# PADS_Schemat.net
KiCad netlist of a schematic drawn in Altium Designer
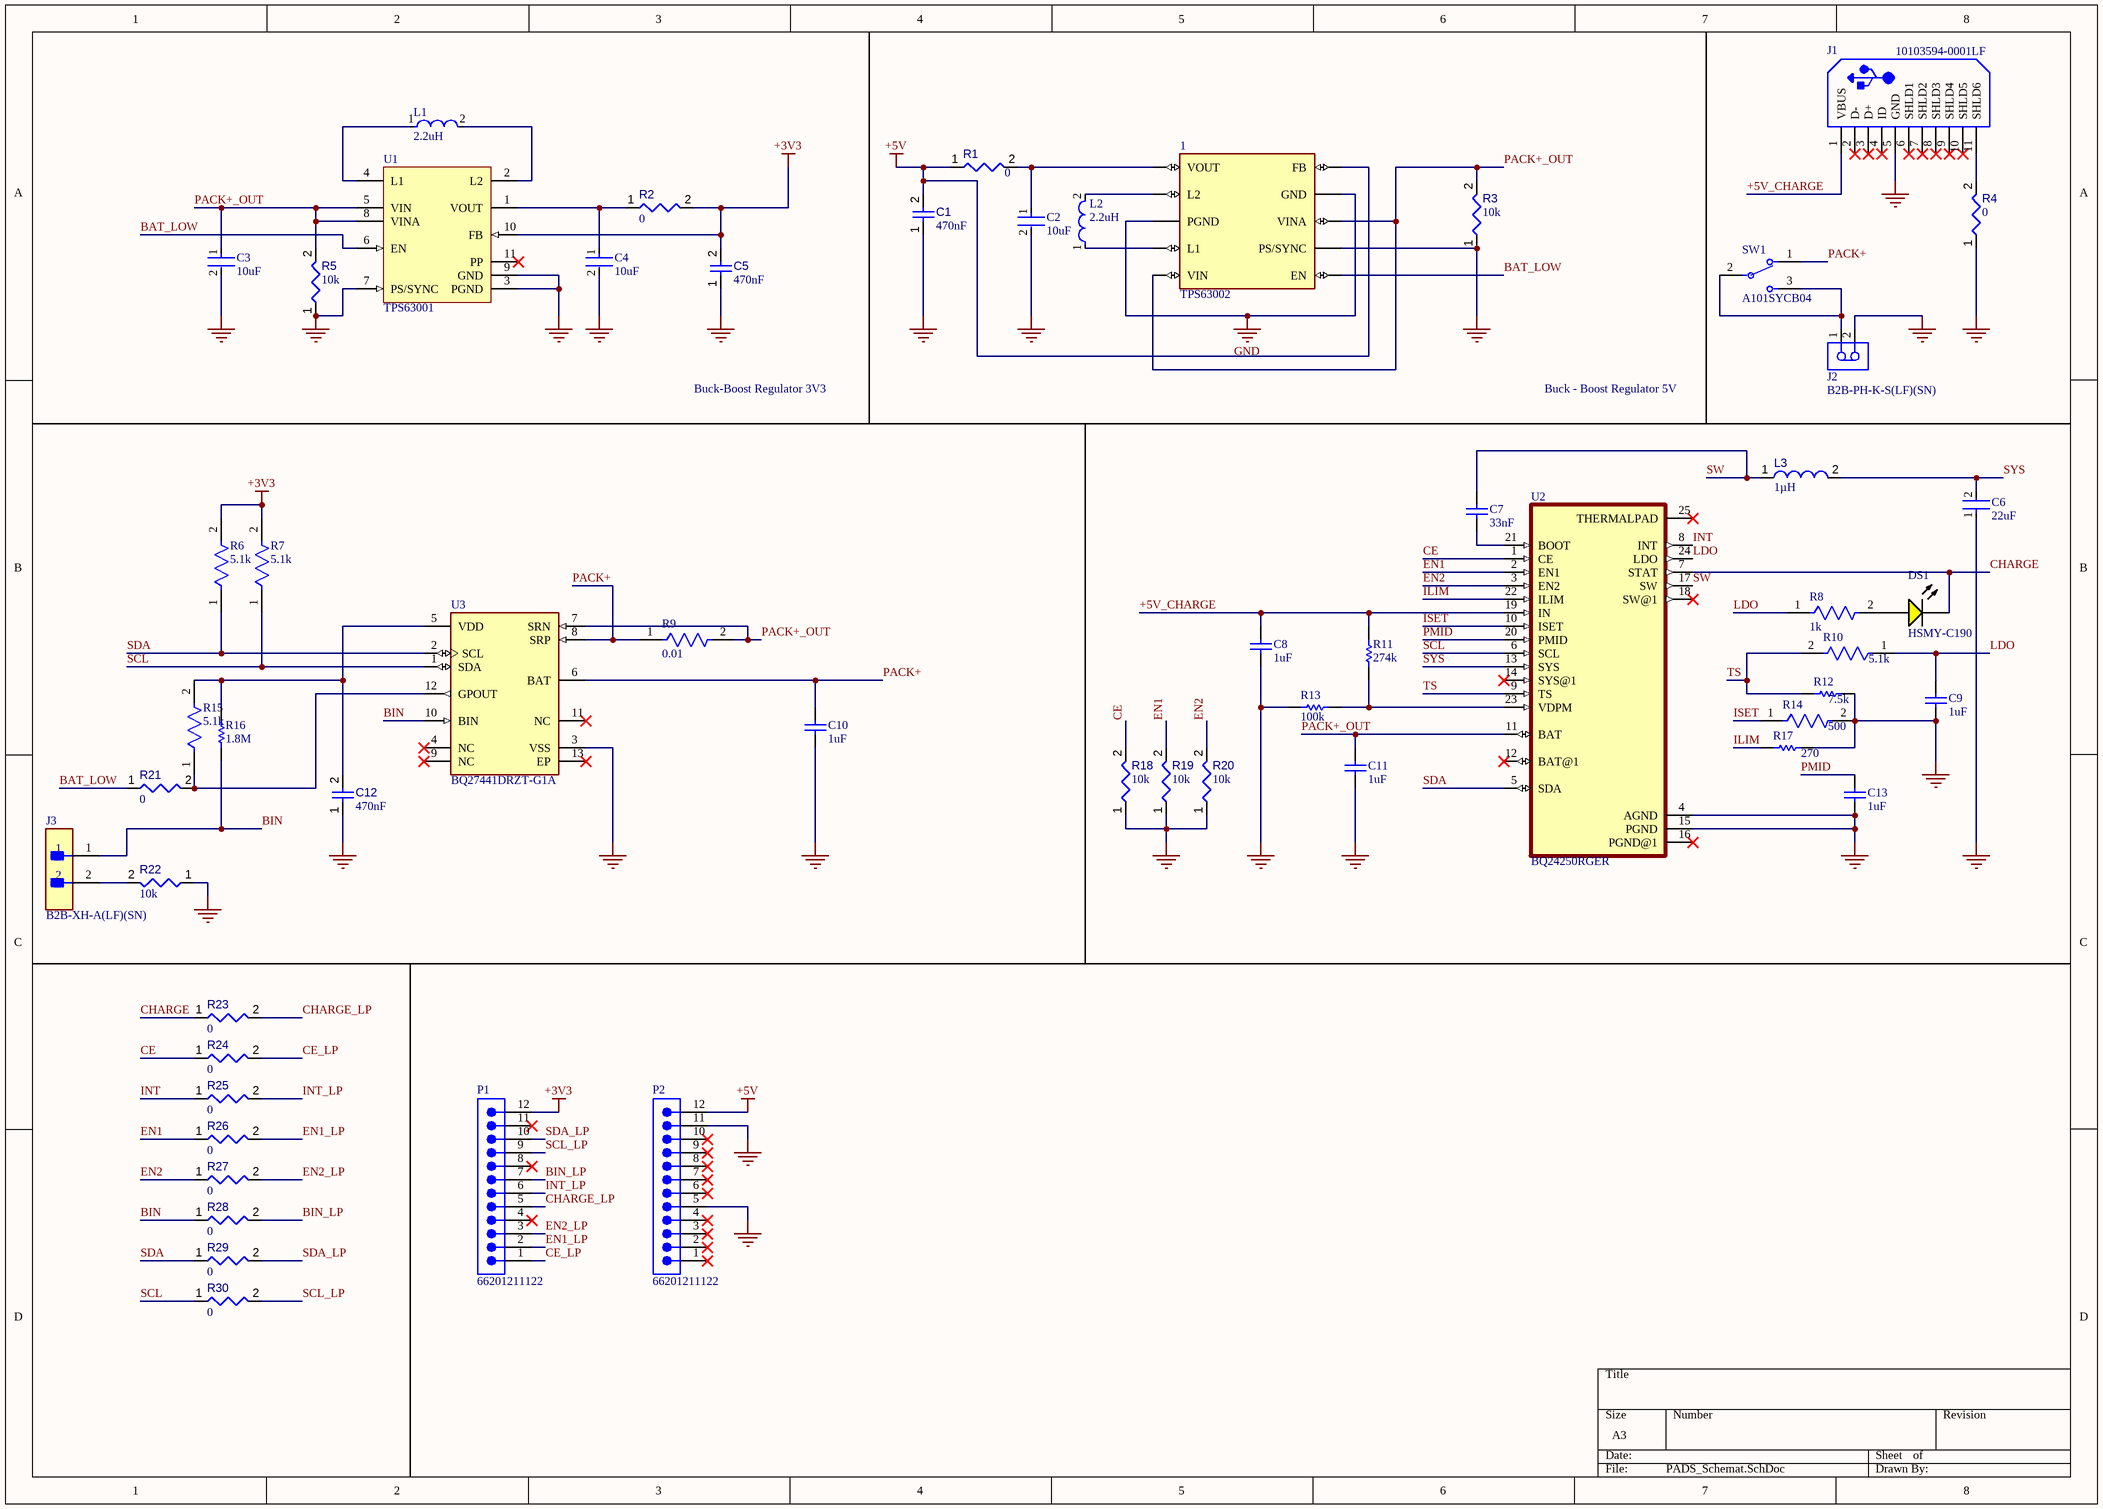
[diagram p0: PADS_Schemat.SchDoc]

(export (version "E")
  (design (tool "Eeschema 10.0.6"))
  (components
    (comp (ref "1")
      (value "TPS63002")
      (footprint "10SON")
      (description "Buck-Boost Switching Regulator IC Positive Fixed 5V 1 Output 1.6A _Switch_ 10-VFDFN Exposed Pad")
      (fields (field (name "MF") "Texas Instruments"))
      (libsource (lib "Przemysław Ziencik") (part "TPS63002"))
    )
    (comp (ref "C1")
      (value "470nF")
      (footprint "CAPC0603(1608)100_L")
      (description "Chip Capacitor, 470nF +/-20%, 25V, 0603, Thickness 1 mm")
      (fields (field (name "TOLERANCE") "10%") (field (name "Comment") "Capacitor 470nF +/-20% 25V 0603"))
      (libsource (lib "Przemysław Ziencik") (part "CAP-NP-2"))
    )
    (comp (ref "C2")
      (value "10uF")
      (footprint "FP-GRM188-0_1-e0_2_0_55-IPC_A")
      (description "Chip Multilayer Ceramic Capacitors for General Purpose, 0603, 10uF, X5R, 15%, 20%, 6.3V")
      (fields (field (name "VOLTAGE") "6.3V") (field (name "TOLERANCE") "20%"))
      (libsource (lib "Altium Content Vault") (part "02cd4be3c70576c341d710602a673aa"))
    )
    (comp (ref "C3")
      (value "10uF")
      (footprint "FP-GRM188-0_1-e0_2_0_55-IPC_A")
      (description "Chip Multilayer Ceramic Capacitors for General Purpose, 0603, 10uF, X5R, 15%, 20%, 6.3V")
      (fields (field (name "VOLTAGE") "6.3V") (field (name "TOLERANCE") "20%"))
      (libsource (lib "Altium Content Vault") (part "02cd4be3c70576c341d710602a673aa"))
    )
    (comp (ref "C4")
      (value "10uF")
      (footprint "FP-GRM188-0_1-e0_2_0_55-IPC_A")
      (description "Chip Multilayer Ceramic Capacitors for General Purpose, 0603, 10uF, X5R, 15%, 20%, 6.3V")
      (fields (field (name "VOLTAGE") "6.3V") (field (name "TOLERANCE") "20%"))
      (libsource (lib "Altium Content Vault") (part "02cd4be3c70576c341d710602a673aa"))
    )
    (comp (ref "C5")
      (value "470nF")
      (footprint "CAPC0603(1608)100_L")
      (description "Chip Capacitor, 470nF +/-20%, 25V, 0603, Thickness 1 mm")
      (fields (field (name "TOLERANCE") "10%") (field (name "Comment") "Capacitor 470nF +/-20% 25V 0603"))
      (libsource (lib "Przemysław Ziencik") (part "CAP-NP-2"))
    )
    (comp (ref "C6")
      (value "22uF")
      (footprint "FP-GRM21B-0_15-MFG")
      (description "Chip Multilayer Ceramic Capacitors for General Purpose, 0805, 22uF, X5R, 15%, 20%, 6.3V")
      (fields (field (name "VOLTAGE") "6.3V") (field (name "TOLERANCE") "20%"))
      (libsource (lib "Altium Content Vault") (part "b4654b650e69147ec39a6b967a45e02"))
    )
    (comp (ref "C7")
      (value "33nF")
      (footprint "CAPC2013X95X45NL10T25")
      (fields (field (name "MANUFACTURER") "Murata") (field (name "PART NUMBER") "GRM219R71H333KA01D"))
      (libsource (lib "Altium Content Vault") (part "CAP"))
    )
    (comp (ref "C8")
      (value "1uF")
      (footprint "CAPC2013X135X45LL10T25")
      (fields (field (name "MANUFACTURER") "Murata") (field (name "PART NUMBER") "GRM21BR71C105KA01K"))
      (libsource (lib "Altium Content Vault") (part "CAP"))
    )
    (comp (ref "C9")
      (value "1uF")
      (footprint "CAPC2013X135X45LL10T25")
      (fields (field (name "MANUFACTURER") "Murata") (field (name "PART NUMBER") "GRM21BR71C105KA01K"))
      (libsource (lib "Altium Content Vault") (part "CAP"))
    )
    (comp (ref "C10")
      (value "1uF")
      (footprint "CAPC2013X135X45LL10T25")
      (fields (field (name "MANUFACTURER") "Murata") (field (name "PART NUMBER") "GRM21BR71C105KA01K"))
      (libsource (lib "Altium Content Vault") (part "CAP"))
    )
    (comp (ref "C11")
      (value "1uF")
      (footprint "CAPC2013X135X45LL10T25")
      (fields (field (name "MANUFACTURER") "Murata") (field (name "PART NUMBER") "GRM21BR71C105KA01K"))
      (libsource (lib "Altium Content Vault") (part "CAP"))
    )
    (comp (ref "C12")
      (value "470nF")
      (footprint "CAPC0603(1608)100_L")
      (description "Chip Capacitor, 470nF +/-20%, 25V, 0603, Thickness 1 mm")
      (fields (field (name "TOLERANCE") "10%") (field (name "Comment") "Capacitor 470nF +/-20% 25V 0603"))
      (libsource (lib "Przemysław Ziencik") (part "CAP-NP-2"))
    )
    (comp (ref "C13")
      (value "1uF")
      (footprint "CAPC2013X135X45LL10T25")
      (fields (field (name "MANUFACTURER") "Murata") (field (name "PART NUMBER") "GRM21BR71C105KA01K"))
      (libsource (lib "Altium Content Vault") (part "CAP"))
    )
    (comp (ref "DS1")
      (value "HSMY-C190")
      (footprint "AVAG-HSMX-C190_V")
      (description "LED Uni-Color Yellow, 65 mW, 20 mA, -40 to 85 degC, 2-Pin SMD, RoHS, Tape and Reel")
      (fields (field (name "TOLERANCE") "1%"))
      (libsource (lib "Altium Content Vault") (part "LED-YELLOW-AK-2"))
    )
    (comp (ref "J1")
      (value "10103594-0001LF")
      (footprint "FCI-10103594-0001LF_V")
      (description "Micro USB 2.0 B Receptacle, 5 Position, Height 3.24 mm, -55 to 85 degC, RoHS, Tape and Reel")
      (fields (field (name "MANUFACTURER") "FCI Electronics"))
      (libsource (lib "Przemysław Ziencik") (part "USB-5-6SHLD"))
    )
    (comp (ref "J2")
      (value "B2B-PH-K-S(LF)(SN)")
      (footprint "JST-B2B-PH-K-S_V")
      (fields (field (name "MANUFACTURER") "JST"))
      (libsource (lib "Altium Content Vault") (part "CN-2P-F-QF2"))
    )
    (comp (ref "J3")
      (value "B2B-XH-A(LF)(SN)")
      (footprint "FP-B2B-XH-A_LF_SN-MFG")
      (description "CONN HEADER VERT 2POS 2.5MM")
      (libsource (lib "Altium Content Vault") (part "3bc925449376181038e59eaffc5286c"))
    )
    (comp (ref "L1")
      (value "2.2uH")
      (footprint "FP-LQM21PH_G0-IPC_C")
      (description "Multilayer Type Inductor for Power Lines, 0805 (2012), 2.2μH, 30%, 0.288Ω, 0.8A")
      (fields (field (name "TOLERANCE") "30%"))
      (libsource (lib "Altium Content Vault") (part "725321dda6339637d4d059423bc1c3c"))
    )
    (comp (ref "L2")
      (value "2.2uH")
      (footprint "FP-LQM21PH_G0-IPC_C")
      (description "Multilayer Type Inductor for Power Lines, 0805 (2012), 2.2μH, 30%, 0.288Ω, 0.8A")
      (fields (field (name "TOLERANCE") "30%"))
      (libsource (lib "Altium Content Vault") (part "725321dda6339637d4d059423bc1c3c"))
    )
    (comp (ref "L3")
      (value "1µH")
      (footprint "INDC2520X120X60NL20T20")
      (description "Chip Inductor, 1 uH, +/- 20%, 1 MHz, -55 to 125 degC, 1008 (2520 Metric), RoHS, Tape and Reel")
      (fields (field (name "TOLERANCE") "20%") (field (name "MANUFACTURER") "Murata"))
      (libsource (lib "Przemysław Ziencik") (part "IND-2"))
    )
    (comp (ref "P1")
      (value "66201211122")
      (footprint "66201211122")
      (libsource (lib "Altium Content Vault") (part "Header_Male_1R_12P"))
    )
    (comp (ref "P2")
      (value "66201211122")
      (footprint "66201211122")
      (libsource (lib "Altium Content Vault") (part "Header_Male_1R_12P"))
    )
    (comp (ref "R1")
      (value "0")
      (footprint "RESC0603(1608)_L")
      (description "Jumper 0603 (1608 Metric)")
      (fields (field (name "Comment") "0R3J"))
      (libsource (lib "Przemysław Ziencik") (part "0R3J"))
    )
    (comp (ref "R2")
      (value "0")
      (footprint "RESC0603(1608)_L")
      (description "Jumper 0603 (1608 Metric)")
      (fields (field (name "Comment") "0R3J"))
      (libsource (lib "Przemysław Ziencik") (part "0R3J"))
    )
    (comp (ref "R3")
      (value "10k")
      (footprint "RESC0402(1005)_L")
      (description "10K 0.063W 1% 0402 (1005 Metric)  SMD")
      (fields (field (name "POWER") "63mW") (field (name "TOLERANCE") "1%"))
      (libsource (lib "Przemysław Ziencik") (part "10KR2F"))
    )
    (comp (ref "R4")
      (value "0")
      (footprint "RESC0603(1608)_L")
      (description "Jumper 0603 (1608 Metric)")
      (fields (field (name "Comment") "0R3J"))
      (libsource (lib "Przemysław Ziencik") (part "0R3J"))
    )
    (comp (ref "R5")
      (value "10k")
      (footprint "RESC0402(1005)_L")
      (description "10K 0.063W 1% 0402 (1005 Metric)  SMD")
      (fields (field (name "POWER") "63mW") (field (name "TOLERANCE") "1%"))
      (libsource (lib "Przemysław Ziencik") (part "10KR2F"))
    )
    (comp (ref "R6")
      (value "5.1k")
      (footprint "FP-CRCW0603-e3-IPC_C")
      (description "RES Thick Film, 5.1kΩ, 1%, 0.1W, 100ppm/°C, 0603")
      (fields (field (name "TOLERANCE") "1%"))
      (libsource (lib "Altium Content Vault") (part "1029c3af85768c4190bb7ad29bc67b5"))
    )
    (comp (ref "R7")
      (value "5.1k")
      (footprint "FP-CRCW0603-e3-IPC_C")
      (description "RES Thick Film, 5.1kΩ, 1%, 0.1W, 100ppm/°C, 0603")
      (fields (field (name "TOLERANCE") "1%"))
      (libsource (lib "Altium Content Vault") (part "1029c3af85768c4190bb7ad29bc67b5"))
    )
    (comp (ref "R8")
      (value "1k")
      (footprint "FP-ERA3A-IPC_C")
      (description "RES SMD 1K OHM 0.1% 1/10W 0603")
      (fields (field (name "TOLERANCE") "0.1%"))
      (libsource (lib "Altium Content Vault") (part "1029c3af85768c4190bb7ad29bc67b5"))
    )
    (comp (ref "R9")
      (value "0.01")
      (footprint "FP-ERJ8CW-MFG")
      (description "RES 0.01 OHM 1% 1W 1206")
      (fields (field (name "TOLERANCE") "1%"))
      (libsource (lib "Altium Content Vault") (part "1029c3af85768c4190bb7ad29bc67b5"))
    )
    (comp (ref "R10")
      (value "5.1k")
      (footprint "FP-CRCW0603-e3-IPC_C")
      (description "RES Thick Film, 5.1kΩ, 1%, 0.1W, 100ppm/°C, 0603")
      (fields (field (name "TOLERANCE") "1%"))
      (libsource (lib "Altium Content Vault") (part "1029c3af85768c4190bb7ad29bc67b5"))
    )
    (comp (ref "R11")
      (value "274k")
      (footprint "RESC1608X55X30NL15T15")
      (fields (field (name "MANUFACTURER") "Panasonic") (field (name "PART NUMBER") "ERJ-3EKF2743V"))
      (libsource (lib "Altium Content Vault") (part "RES"))
    )
    (comp (ref "R12")
      (value "7.5k")
      (footprint "RESC1609X55X30NL10T20")
      (fields (field (name "PART NUMBER") "TNPW06037K50BEEA") (field (name "MANUFACTURER") "Vishay Dale"))
      (libsource (lib "Altium Content Vault") (part "RES"))
    )
    (comp (ref "R13")
      (value "100k")
      (footprint "RESC2013X70X40NL20T20")
      (fields (field (name "PART NUMBER") "ERJ-6GEYJ104V") (field (name "MANUFACTURER") "Panasonic"))
      (libsource (lib "Altium Content Vault") (part "RES"))
    )
    (comp (ref "R14")
      (value "500")
      (footprint "FP-MCT0603-MFG")
      (description "RES SMD 100 OHM 1% 1/8W 0603")
      (fields (field (name "TOLERANCE") "0.1%"))
      (libsource (lib "Altium Content Vault") (part "1029c3af85768c4190bb7ad29bc67b5"))
    )
    (comp (ref "R15")
      (value "5.1k")
      (footprint "FP-CRCW0603-e3-IPC_C")
      (description "RES Thick Film, 5.1kΩ, 1%, 0.1W, 100ppm/°C, 0603")
      (fields (field (name "TOLERANCE") "1%"))
      (libsource (lib "Altium Content Vault") (part "1029c3af85768c4190bb7ad29bc67b5"))
    )
    (comp (ref "R16")
      (value "1.8M")
      (footprint "RESC1608X55X30ML15T15")
      (fields (field (name "MANUFACTURER") "Panasonic") (field (name "PART NUMBER") "ERJ-3EKF1804V"))
      (libsource (lib "Altium Content Vault") (part "RES"))
    )
    (comp (ref "R17")
      (value "270")
      (footprint "RESC1608X55X30LL15T15")
      (fields (field (name "MANUFACTURER") "Panasonic") (field (name "PART NUMBER") "ERJ3EKF2700V"))
      (libsource (lib "Altium Content Vault") (part "RES"))
    )
    (comp (ref "R18")
      (value "10k")
      (footprint "RESC0402(1005)_L")
      (description "10K 0.063W 1% 0402 (1005 Metric)  SMD")
      (fields (field (name "POWER") "63mW") (field (name "TOLERANCE") "1%"))
      (libsource (lib "Przemysław Ziencik") (part "10KR2F"))
    )
    (comp (ref "R19")
      (value "10k")
      (footprint "RESC0402(1005)_L")
      (description "10K 0.063W 1% 0402 (1005 Metric)  SMD")
      (fields (field (name "POWER") "63mW") (field (name "TOLERANCE") "1%"))
      (libsource (lib "Przemysław Ziencik") (part "10KR2F"))
    )
    (comp (ref "R20")
      (value "10k")
      (footprint "RESC0402(1005)_L")
      (description "10K 0.063W 1% 0402 (1005 Metric)  SMD")
      (fields (field (name "POWER") "63mW") (field (name "TOLERANCE") "1%"))
      (libsource (lib "Przemysław Ziencik") (part "10KR2F"))
    )
    (comp (ref "R21")
      (value "0")
      (footprint "RESC0603(1608)_L")
      (description "Jumper 0603 (1608 Metric)")
      (fields (field (name "Comment") "0R3J"))
      (libsource (lib "Przemysław Ziencik") (part "0R3J"))
    )
    (comp (ref "R22")
      (value "10k")
      (footprint "RESC0402(1005)_L")
      (description "10K 0.063W 1% 0402 (1005 Metric)  SMD")
      (fields (field (name "POWER") "63mW") (field (name "TOLERANCE") "1%"))
      (libsource (lib "Przemysław Ziencik") (part "10KR2F"))
    )
    (comp (ref "R23")
      (value "0")
      (footprint "RESC0603(1608)_L")
      (description "Jumper 0603 (1608 Metric)")
      (fields (field (name "Comment") "0R3J"))
      (libsource (lib "Przemysław Ziencik") (part "0R3J"))
    )
    (comp (ref "R24")
      (value "0")
      (footprint "RESC0603(1608)_L")
      (description "Jumper 0603 (1608 Metric)")
      (fields (field (name "Comment") "0R3J"))
      (libsource (lib "Przemysław Ziencik") (part "0R3J"))
    )
    (comp (ref "R25")
      (value "0")
      (footprint "RESC0603(1608)_L")
      (description "Jumper 0603 (1608 Metric)")
      (fields (field (name "Comment") "0R3J"))
      (libsource (lib "Przemysław Ziencik") (part "0R3J"))
    )
    (comp (ref "R26")
      (value "0")
      (footprint "RESC0603(1608)_L")
      (description "Jumper 0603 (1608 Metric)")
      (fields (field (name "Comment") "0R3J"))
      (libsource (lib "Przemysław Ziencik") (part "0R3J"))
    )
    (comp (ref "R27")
      (value "0")
      (footprint "RESC0603(1608)_L")
      (description "Jumper 0603 (1608 Metric)")
      (fields (field (name "Comment") "0R3J"))
      (libsource (lib "Przemysław Ziencik") (part "0R3J"))
    )
    (comp (ref "R28")
      (value "0")
      (footprint "RESC0603(1608)_L")
      (description "Jumper 0603 (1608 Metric)")
      (fields (field (name "Comment") "0R3J"))
      (libsource (lib "Przemysław Ziencik") (part "0R3J"))
    )
    (comp (ref "R29")
      (value "0")
      (footprint "RESC0603(1608)_L")
      (description "Jumper 0603 (1608 Metric)")
      (fields (field (name "Comment") "0R3J"))
      (libsource (lib "Przemysław Ziencik") (part "0R3J"))
    )
    (comp (ref "R30")
      (value "0")
      (footprint "RESC0603(1608)_L")
      (description "Jumper 0603 (1608 Metric)")
      (fields (field (name "Comment") "0R3J"))
      (libsource (lib "Przemysław Ziencik") (part "0R3J"))
    )
    (comp (ref "SW1")
      (value "A101SYCB04")
      (footprint "FP-A101SYCB04-MFG")
      (description "SWITCH TOGGLE SPDT 0.4VA 20V")
      (libsource (lib "Altium Content Vault") (part "52c419afdc2a387c7d548259a9aeefb"))
    )
    (comp (ref "U1")
      (value "TPS63001")
      (footprint "DRC0010J_V")
      (fields (field (name "PARTNUMBER") "TPS63001DRCR") (field (name "MANUFACTURER") "Texas Instruments"))
      (libsource (lib "Altium Content Vault") (part "TI-TPS63001DRC10-3000X1650TP"))
    )
    (comp (ref "U2")
      (value "BQ24250RGER")
      (footprint "QFN50P400X400X100-25N")
      (fields (field (name "MF") "Texas Instruments"))
      (libsource (lib "BQ24250RGER") (part "BQ24250RGER"))
    )
    (comp (ref "U3")
      (value "BQ27441DRZT-G1A")
      (footprint "FP-DRZ0012A-MFG")
      (description "IC BATT FUEL GAUGE LICOO2 12SON")
      (fields
        (field (name "OCTOPART") "https://octopart.com/bq27441drzt-g1a-texas+instruments-30555831")
        (field (name "MANUFACTURER") "Texas Instruments")
      )
      (libsource (lib "Altium Content Vault") (part "c803e035ce0891ae19034f27297cdee"))
    )
  )
  (nets
    (net (code "1") (name "+3V3") (class "Default")
      (node (ref "C5") (pin "2") (pinfunction "2_2") (pintype "passive"))
      (node (ref "P1") (pin "12") (pinfunction "12_12") (pintype "passive"))
      (node (ref "R2") (pin "2") (pinfunction "2_2") (pintype "passive"))
      (node (ref "R6") (pin "2") (pinfunction "2_2") (pintype "passive"))
      (node (ref "R7") (pin "2") (pinfunction "2_2") (pintype "passive"))
      (node (ref "U1") (pin "10") (pinfunction "FB_10") (pintype "input"))
    )
    (net (code "2") (name "+5V") (class "Default")
      (node (ref "1") (pin "P$10") (pinfunction "FB_P$10") (pintype "bidirectional"))
      (node (ref "C1") (pin "2") (pinfunction "2_2") (pintype "passive"))
      (node (ref "P2") (pin "12") (pinfunction "12_12") (pintype "passive"))
      (node (ref "R1") (pin "1") (pinfunction "1_1") (pintype "passive"))
    )
    (net (code "3") (name "/+5V_CHARGE") (class "Default")
      (node (ref "C8") (pin "2") (pinfunction "2_2") (pintype "passive"))
      (node (ref "J1") (pin "1") (pinfunction "VBUS_1") (pintype "passive"))
      (node (ref "R11") (pin "2") (pinfunction "2_2") (pintype "passive"))
      (node (ref "U2") (pin "19") (pinfunction "IN_19") (pintype "input"))
    )
    (net (code "4") (name "/BAT_LOW") (class "Default")
      (node (ref "1") (pin "P$6") (pinfunction "EN_P$6") (pintype "bidirectional"))
      (node (ref "R21") (pin "1") (pinfunction "1_1") (pintype "passive"))
      (node (ref "U1") (pin "6") (pinfunction "EN_6") (pintype "input"))
    )
    (net (code "5") (name "/BIN") (class "Default")
      (node (ref "J3") (pin "1") (pinfunction "1_1") (pintype "passive"))
      (node (ref "R16") (pin "1") (pinfunction "1_1") (pintype "passive"))
      (node (ref "R28") (pin "1") (pinfunction "1_1") (pintype "passive"))
      (node (ref "U3") (pin "10") (pinfunction "BIN_10") (pintype "input"))
    )
    (net (code "6") (name "/BIN_LP") (class "Default")
      (node (ref "P1") (pin "7") (pinfunction "7_7") (pintype "passive"))
      (node (ref "R28") (pin "2") (pinfunction "2_2") (pintype "passive"))
    )
    (net (code "7") (name "/CE") (class "Default")
      (node (ref "R18") (pin "2") (pinfunction "2_2") (pintype "passive"))
      (node (ref "R24") (pin "1") (pinfunction "1_1") (pintype "passive"))
      (node (ref "U2") (pin "1") (pinfunction "CE_1") (pintype "input"))
    )
    (net (code "8") (name "/CE_LP") (class "Default")
      (node (ref "P1") (pin "1") (pinfunction "1_1") (pintype "passive"))
      (node (ref "R24") (pin "2") (pinfunction "2_2") (pintype "passive"))
    )
    (net (code "9") (name "/CHARGE") (class "Default")
      (node (ref "DS1") (pin "2") (pinfunction "K_2") (pintype "passive"))
      (node (ref "R23") (pin "1") (pinfunction "1_1") (pintype "passive"))
      (node (ref "U2") (pin "7") (pinfunction "STAT_7") (pintype "output"))
    )
    (net (code "10") (name "/CHARGE_LP") (class "Default")
      (node (ref "P1") (pin "5") (pinfunction "5_5") (pintype "passive"))
      (node (ref "R23") (pin "2") (pinfunction "2_2") (pintype "passive"))
    )
    (net (code "11") (name "/EN1") (class "Default")
      (node (ref "R19") (pin "2") (pinfunction "2_2") (pintype "passive"))
      (node (ref "R26") (pin "1") (pinfunction "1_1") (pintype "passive"))
      (node (ref "U2") (pin "2") (pinfunction "EN1_2") (pintype "input"))
    )
    (net (code "12") (name "/EN1_LP") (class "Default")
      (node (ref "P1") (pin "2") (pinfunction "2_2") (pintype "passive"))
      (node (ref "R26") (pin "2") (pinfunction "2_2") (pintype "passive"))
    )
    (net (code "13") (name "/EN2") (class "Default")
      (node (ref "R20") (pin "2") (pinfunction "2_2") (pintype "passive"))
      (node (ref "R27") (pin "1") (pinfunction "1_1") (pintype "passive"))
      (node (ref "U2") (pin "3") (pinfunction "EN2_3") (pintype "input"))
    )
    (net (code "14") (name "/EN2_LP") (class "Default")
      (node (ref "P1") (pin "3") (pinfunction "3_3") (pintype "passive"))
      (node (ref "R27") (pin "2") (pinfunction "2_2") (pintype "passive"))
    )
    (net (code "15") (name "/ILIM") (class "Default")
      (node (ref "R17") (pin "1") (pinfunction "1_1") (pintype "passive"))
      (node (ref "U2") (pin "22") (pinfunction "ILIM_22") (pintype "input"))
    )
    (net (code "16") (name "/INT") (class "Default")
      (node (ref "R25") (pin "1") (pinfunction "1_1") (pintype "passive"))
      (node (ref "U2") (pin "8") (pinfunction "INT_8") (pintype "output"))
    )
    (net (code "17") (name "/INT_LP") (class "Default")
      (node (ref "P1") (pin "6") (pinfunction "6_6") (pintype "passive"))
      (node (ref "R25") (pin "2") (pinfunction "2_2") (pintype "passive"))
    )
    (net (code "18") (name "/ISET") (class "Default")
      (node (ref "R14") (pin "1") (pinfunction "1_1") (pintype "passive"))
      (node (ref "U2") (pin "10") (pinfunction "ISET_10") (pintype "input"))
    )
    (net (code "19") (name "/LDO") (class "Default")
      (node (ref "C9") (pin "2") (pinfunction "2_2") (pintype "passive"))
      (node (ref "R10") (pin "1") (pinfunction "1_1") (pintype "passive"))
      (node (ref "R8") (pin "1") (pinfunction "1_1") (pintype "passive"))
      (node (ref "U2") (pin "24") (pinfunction "LDO_24") (pintype "output"))
    )
    (net (code "20") (name "/PACK+") (class "Default")
      (node (ref "C10") (pin "2") (pinfunction "2_2") (pintype "passive"))
      (node (ref "R9") (pin "1") (pinfunction "1_1") (pintype "passive"))
      (node (ref "SW1") (pin "1") (pinfunction "1_1") (pintype "passive"))
      (node (ref "U3") (pin "6") (pinfunction "BAT_6") (pintype "power_in"))
      (node (ref "U3") (pin "8") (pinfunction "SRP_8") (pintype "input"))
    )
    (net (code "21") (name "/PACK+_OUT") (class "Default")
      (node (ref "1") (pin "P$5") (pinfunction "VIN_P$5") (pintype "bidirectional"))
      (node (ref "1") (pin "P$8") (pinfunction "VINA_P$8") (pintype "bidirectional"))
      (node (ref "C11") (pin "2") (pinfunction "2_2") (pintype "passive"))
      (node (ref "C3") (pin "1") (pinfunction "1_1") (pintype "passive"))
      (node (ref "R3") (pin "2") (pinfunction "2_2") (pintype "passive"))
      (node (ref "R5") (pin "2") (pinfunction "2_2") (pintype "passive"))
      (node (ref "R9") (pin "2") (pinfunction "2_2") (pintype "passive"))
      (node (ref "U1") (pin "5") (pinfunction "VIN_5") (pintype "passive"))
      (node (ref "U1") (pin "8") (pinfunction "VINA_8") (pintype "passive"))
      (node (ref "U2") (pin "11") (pinfunction "BAT_11") (pintype "bidirectional"))
      (node (ref "U3") (pin "7") (pinfunction "SRN_7") (pintype "input"))
    )
    (net (code "22") (name "/PMID") (class "Default")
      (node (ref "C13") (pin "2") (pinfunction "2_2") (pintype "passive"))
      (node (ref "U2") (pin "20") (pinfunction "PMID_20") (pintype "input"))
    )
    (net (code "23") (name "/SCL") (class "Default")
      (node (ref "R30") (pin "1") (pinfunction "1_1") (pintype "passive"))
      (node (ref "R7") (pin "1") (pinfunction "1_1") (pintype "passive"))
      (node (ref "U2") (pin "6") (pinfunction "SCL_6") (pintype "input"))
      (node (ref "U3") (pin "1") (pinfunction "SDA_1") (pintype "bidirectional"))
    )
    (net (code "24") (name "/SCL_LP") (class "Default")
      (node (ref "P1") (pin "9") (pinfunction "9_9") (pintype "passive"))
      (node (ref "R30") (pin "2") (pinfunction "2_2") (pintype "passive"))
    )
    (net (code "25") (name "/SDA") (class "Default")
      (node (ref "R29") (pin "1") (pinfunction "1_1") (pintype "passive"))
      (node (ref "R6") (pin "1") (pinfunction "1_1") (pintype "passive"))
      (node (ref "U2") (pin "5") (pinfunction "SDA_5") (pintype "bidirectional"))
      (node (ref "U3") (pin "2") (pinfunction "SCL_2") (pintype "bidirectional"))
    )
    (net (code "26") (name "/SDA_LP") (class "Default")
      (node (ref "P1") (pin "10") (pinfunction "10_10") (pintype "passive"))
      (node (ref "R29") (pin "2") (pinfunction "2_2") (pintype "passive"))
    )
    (net (code "27") (name "/SW") (class "Default")
      (node (ref "C7") (pin "2") (pinfunction "2_2") (pintype "passive"))
      (node (ref "L3") (pin "1") (pinfunction "1_1") (pintype "passive"))
      (node (ref "U2") (pin "17") (pinfunction "SW_17") (pintype "output"))
    )
    (net (code "28") (name "/SYS") (class "Default")
      (node (ref "C6") (pin "2") (pinfunction "2_2") (pintype "passive"))
      (node (ref "L3") (pin "2") (pinfunction "2_2") (pintype "passive"))
      (node (ref "U2") (pin "13") (pinfunction "SYS_13") (pintype "input"))
    )
    (net (code "29") (name "/TS") (class "Default")
      (node (ref "R10") (pin "2") (pinfunction "2_2") (pintype "passive"))
      (node (ref "R12") (pin "1") (pinfunction "1_1") (pintype "passive"))
      (node (ref "U2") (pin "9") (pinfunction "TS_9") (pintype "input"))
    )
    (net (code "30") (name "GND") (class "Default")
      (node (ref "1") (pin "P$3") (pinfunction "PGND_P$3") (pintype "passive"))
      (node (ref "1") (pin "P$7") (pinfunction "PS/SYNC_P$7") (pintype "passive"))
      (node (ref "1") (pin "P$9") (pinfunction "GND_P$9") (pintype "passive"))
      (node (ref "C1") (pin "1") (pinfunction "1_1") (pintype "passive"))
      (node (ref "C10") (pin "1") (pinfunction "1_1") (pintype "passive"))
      (node (ref "C11") (pin "1") (pinfunction "1_1") (pintype "passive"))
      (node (ref "C12") (pin "1") (pinfunction "1_1") (pintype "passive"))
      (node (ref "C13") (pin "1") (pinfunction "1_1") (pintype "passive"))
      (node (ref "C2") (pin "2") (pinfunction "2_2") (pintype "passive"))
      (node (ref "C3") (pin "2") (pinfunction "2_2") (pintype "passive"))
      (node (ref "C4") (pin "2") (pinfunction "2_2") (pintype "passive"))
      (node (ref "C5") (pin "1") (pinfunction "1_1") (pintype "passive"))
      (node (ref "C6") (pin "1") (pinfunction "1_1") (pintype "passive"))
      (node (ref "C8") (pin "1") (pinfunction "1_1") (pintype "passive"))
      (node (ref "C9") (pin "1") (pinfunction "1_1") (pintype "passive"))
      (node (ref "J1") (pin "5") (pinfunction "GND_5") (pintype "passive"))
      (node (ref "J2") (pin "2") (pinfunction "2_2") (pintype "passive"))
      (node (ref "P2") (pin "11") (pinfunction "11_11") (pintype "passive"))
      (node (ref "P2") (pin "5") (pinfunction "5_5") (pintype "passive"))
      (node (ref "R12") (pin "2") (pinfunction "2_2") (pintype "passive"))
      (node (ref "R13") (pin "1") (pinfunction "1_1") (pintype "passive"))
      (node (ref "R14") (pin "2") (pinfunction "2_2") (pintype "passive"))
      (node (ref "R17") (pin "2") (pinfunction "2_2") (pintype "passive"))
      (node (ref "R18") (pin "1") (pinfunction "1_1") (pintype "passive"))
      (node (ref "R19") (pin "1") (pinfunction "1_1") (pintype "passive"))
      (node (ref "R20") (pin "1") (pinfunction "1_1") (pintype "passive"))
      (node (ref "R22") (pin "1") (pinfunction "1_1") (pintype "passive"))
      (node (ref "R3") (pin "1") (pinfunction "1_1") (pintype "passive"))
      (node (ref "R4") (pin "1") (pinfunction "1_1") (pintype "passive"))
      (node (ref "R5") (pin "1") (pinfunction "1_1") (pintype "passive"))
      (node (ref "U1") (pin "3") (pinfunction "PGND_3") (pintype "passive"))
      (node (ref "U1") (pin "7") (pinfunction "PS/SYNC_7") (pintype "input"))
      (node (ref "U1") (pin "9") (pinfunction "GND_9") (pintype "passive"))
      (node (ref "U2") (pin "15") (pinfunction "PGND_15") (pintype "power_in"))
      (node (ref "U2") (pin "4") (pinfunction "AGND_4") (pintype "power_in"))
      (node (ref "U3") (pin "3") (pinfunction "VSS_3") (pintype "power_in"))
    )
    (net (code "31") (name "Net-(1-L1)") (class "Default")
      (node (ref "1") (pin "P$4") (pinfunction "L1_P$4") (pintype "bidirectional"))
      (node (ref "L2") (pin "1") (pinfunction "1_1") (pintype "passive"))
    )
    (net (code "32") (name "Net-(1-L2)") (class "Default")
      (node (ref "1") (pin "P$2") (pinfunction "L2_P$2") (pintype "bidirectional"))
      (node (ref "L2") (pin "2") (pinfunction "2_2") (pintype "passive"))
    )
    (net (code "33") (name "Net-(1-VOUT)") (class "Default")
      (node (ref "1") (pin "P$1") (pinfunction "VOUT_P$1") (pintype "bidirectional"))
      (node (ref "C2") (pin "1") (pinfunction "1_1") (pintype "passive"))
      (node (ref "R1") (pin "2") (pinfunction "2_2") (pintype "passive"))
    )
    (net (code "34") (name "Net-(DS1-A)") (class "Default")
      (node (ref "DS1") (pin "1") (pinfunction "A_1") (pintype "passive"))
      (node (ref "R8") (pin "2") (pinfunction "2_2") (pintype "passive"))
    )
    (net (code "35") (name "Net-(J1-SHLD6)") (class "Default")
      (node (ref "J1") (pin "11") (pinfunction "SHLD6_11") (pintype "passive"))
      (node (ref "R4") (pin "2") (pinfunction "2_2") (pintype "passive"))
    )
    (net (code "36") (name "Net-(J2-Pad1)") (class "Default")
      (node (ref "J2") (pin "1") (pinfunction "1_1") (pintype "passive"))
      (node (ref "SW1") (pin "2") (pinfunction "2_2") (pintype "passive"))
      (node (ref "SW1") (pin "3") (pinfunction "3_3") (pintype "passive"))
    )
    (net (code "37") (name "Net-(J3-Pad2)") (class "Default")
      (node (ref "J3") (pin "2") (pinfunction "2_2") (pintype "passive"))
      (node (ref "R22") (pin "2") (pinfunction "2_2") (pintype "passive"))
    )
    (net (code "38") (name "Net-(U1-L1)") (class "Default")
      (node (ref "L1") (pin "1") (pinfunction "1_1") (pintype "passive"))
      (node (ref "U1") (pin "4") (pinfunction "L1_4") (pintype "passive"))
    )
    (net (code "39") (name "Net-(U1-L2)") (class "Default")
      (node (ref "L1") (pin "2") (pinfunction "2_2") (pintype "passive"))
      (node (ref "U1") (pin "2") (pinfunction "L2_2") (pintype "passive"))
    )
    (net (code "40") (name "Net-(U1-VOUT)") (class "Default")
      (node (ref "C4") (pin "1") (pinfunction "1_1") (pintype "passive"))
      (node (ref "R2") (pin "1") (pinfunction "1_1") (pintype "passive"))
      (node (ref "U1") (pin "1") (pinfunction "VOUT_1") (pintype "power_in"))
    )
    (net (code "41") (name "Net-(U2-BOOT)") (class "Default")
      (node (ref "C7") (pin "1") (pinfunction "1_1") (pintype "passive"))
      (node (ref "U2") (pin "21") (pinfunction "BOOT_21") (pintype "input"))
    )
    (net (code "42") (name "Net-(U2-VDPM)") (class "Default")
      (node (ref "R11") (pin "1") (pinfunction "1_1") (pintype "passive"))
      (node (ref "R13") (pin "2") (pinfunction "2_2") (pintype "passive"))
      (node (ref "U2") (pin "23") (pinfunction "VDPM_23") (pintype "input"))
    )
    (net (code "43") (name "Net-(U3-GPOUT)") (class "Default")
      (node (ref "R15") (pin "1") (pinfunction "1_1") (pintype "passive"))
      (node (ref "R21") (pin "2") (pinfunction "2_2") (pintype "passive"))
      (node (ref "U3") (pin "12") (pinfunction "GPOUT_12") (pintype "output"))
    )
    (net (code "44") (name "Net-(U3-VDD)") (class "Default")
      (node (ref "C12") (pin "2") (pinfunction "2_2") (pintype "passive"))
      (node (ref "R15") (pin "2") (pinfunction "2_2") (pintype "passive"))
      (node (ref "R16") (pin "2") (pinfunction "2_2") (pintype "passive"))
      (node (ref "U3") (pin "5") (pinfunction "VDD_5") (pintype "power_in"))
    )
    (net (code "45") (name "unconnected-(J1-D+-Pad3)") (class "Default")
      (node (ref "J1") (pin "3") (pinfunction "D+_3") (pintype "passive+no_connect"))
    )
    (net (code "46") (name "unconnected-(J1-D--Pad2)") (class "Default")
      (node (ref "J1") (pin "2") (pinfunction "D-_2") (pintype "passive+no_connect"))
    )
    (net (code "47") (name "unconnected-(J1-ID-Pad4)") (class "Default")
      (node (ref "J1") (pin "4") (pinfunction "ID_4") (pintype "passive+no_connect"))
    )
    (net (code "48") (name "unconnected-(J1-SHLD1-Pad6)") (class "Default")
      (node (ref "J1") (pin "6") (pinfunction "SHLD1_6") (pintype "passive+no_connect"))
    )
    (net (code "49") (name "unconnected-(J1-SHLD2-Pad7)") (class "Default")
      (node (ref "J1") (pin "7") (pinfunction "SHLD2_7") (pintype "passive+no_connect"))
    )
    (net (code "50") (name "unconnected-(J1-SHLD3-Pad8)") (class "Default")
      (node (ref "J1") (pin "8") (pinfunction "SHLD3_8") (pintype "passive+no_connect"))
    )
    (net (code "51") (name "unconnected-(J1-SHLD4-Pad9)") (class "Default")
      (node (ref "J1") (pin "9") (pinfunction "SHLD4_9") (pintype "passive+no_connect"))
    )
    (net (code "52") (name "unconnected-(J1-SHLD5-Pad10)") (class "Default")
      (node (ref "J1") (pin "10") (pinfunction "SHLD5_10") (pintype "passive+no_connect"))
    )
    (net (code "53") (name "unconnected-(P1-Pad4)") (class "Default")
      (node (ref "P1") (pin "4") (pinfunction "4_4") (pintype "passive+no_connect"))
    )
    (net (code "54") (name "unconnected-(P1-Pad8)") (class "Default")
      (node (ref "P1") (pin "8") (pinfunction "8_8") (pintype "passive+no_connect"))
    )
    (net (code "55") (name "unconnected-(P1-Pad11)") (class "Default")
      (node (ref "P1") (pin "11") (pinfunction "11_11") (pintype "passive+no_connect"))
    )
    (net (code "56") (name "unconnected-(P2-Pad1)") (class "Default")
      (node (ref "P2") (pin "1") (pinfunction "1_1") (pintype "passive+no_connect"))
    )
    (net (code "57") (name "unconnected-(P2-Pad2)") (class "Default")
      (node (ref "P2") (pin "2") (pinfunction "2_2") (pintype "passive+no_connect"))
    )
    (net (code "58") (name "unconnected-(P2-Pad3)") (class "Default")
      (node (ref "P2") (pin "3") (pinfunction "3_3") (pintype "passive+no_connect"))
    )
    (net (code "59") (name "unconnected-(P2-Pad4)") (class "Default")
      (node (ref "P2") (pin "4") (pinfunction "4_4") (pintype "passive+no_connect"))
    )
    (net (code "60") (name "unconnected-(P2-Pad6)") (class "Default")
      (node (ref "P2") (pin "6") (pinfunction "6_6") (pintype "passive+no_connect"))
    )
    (net (code "61") (name "unconnected-(P2-Pad7)") (class "Default")
      (node (ref "P2") (pin "7") (pinfunction "7_7") (pintype "passive+no_connect"))
    )
    (net (code "62") (name "unconnected-(P2-Pad8)") (class "Default")
      (node (ref "P2") (pin "8") (pinfunction "8_8") (pintype "passive+no_connect"))
    )
    (net (code "63") (name "unconnected-(P2-Pad9)") (class "Default")
      (node (ref "P2") (pin "9") (pinfunction "9_9") (pintype "passive+no_connect"))
    )
    (net (code "64") (name "unconnected-(P2-Pad10)") (class "Default")
      (node (ref "P2") (pin "10") (pinfunction "10_10") (pintype "passive+no_connect"))
    )
    (net (code "65") (name "unconnected-(U1-PP-Pad11)") (class "Default")
      (node (ref "U1") (pin "11") (pinfunction "PP_11") (pintype "power_in+no_connect"))
    )
    (net (code "66") (name "unconnected-(U2-BAT@1-Pad12)") (class "Default")
      (node (ref "U2") (pin "12") (pinfunction "BAT@1_12") (pintype "bidirectional+no_connect"))
    )
    (net (code "67") (name "unconnected-(U2-PGND@1-Pad16)") (class "Default")
      (node (ref "U2") (pin "16") (pinfunction "PGND@1_16") (pintype "power_in+no_connect"))
    )
    (net (code "68") (name "unconnected-(U2-SW@1-Pad18)") (class "Default")
      (node (ref "U2") (pin "18") (pinfunction "SW@1_18") (pintype "output+no_connect"))
    )
    (net (code "69") (name "unconnected-(U2-SYS@1-Pad14)") (class "Default")
      (node (ref "U2") (pin "14") (pinfunction "SYS@1_14") (pintype "input+no_connect"))
    )
    (net (code "70") (name "unconnected-(U2-THERMALPAD-Pad25)") (class "Default")
      (node (ref "U2") (pin "25") (pinfunction "THERMALPAD_25") (pintype "power_in+no_connect"))
    )
    (net (code "71") (name "unconnected-(U3-EP-Pad13)") (class "Default")
      (node (ref "U3") (pin "13") (pinfunction "EP_13") (pintype "power_in+no_connect"))
    )
    (net (code "72") (name "unconnected-(U3-NC-Pad4)") (class "Default")
      (node (ref "U3") (pin "4") (pinfunction "NC_4") (pintype "passive+no_connect"))
    )
    (net (code "73") (name "unconnected-(U3-NC-Pad9)") (class "Default")
      (node (ref "U3") (pin "9") (pinfunction "NC_9") (pintype "power_in+no_connect"))
    )
    (net (code "74") (name "unconnected-(U3-NC-Pad11)") (class "Default")
      (node (ref "U3") (pin "11") (pinfunction "NC_11") (pintype "passive+no_connect"))
    )
  )
)
